# uartConverter.net
KiCad netlist of a schematic drawn in EAGLE
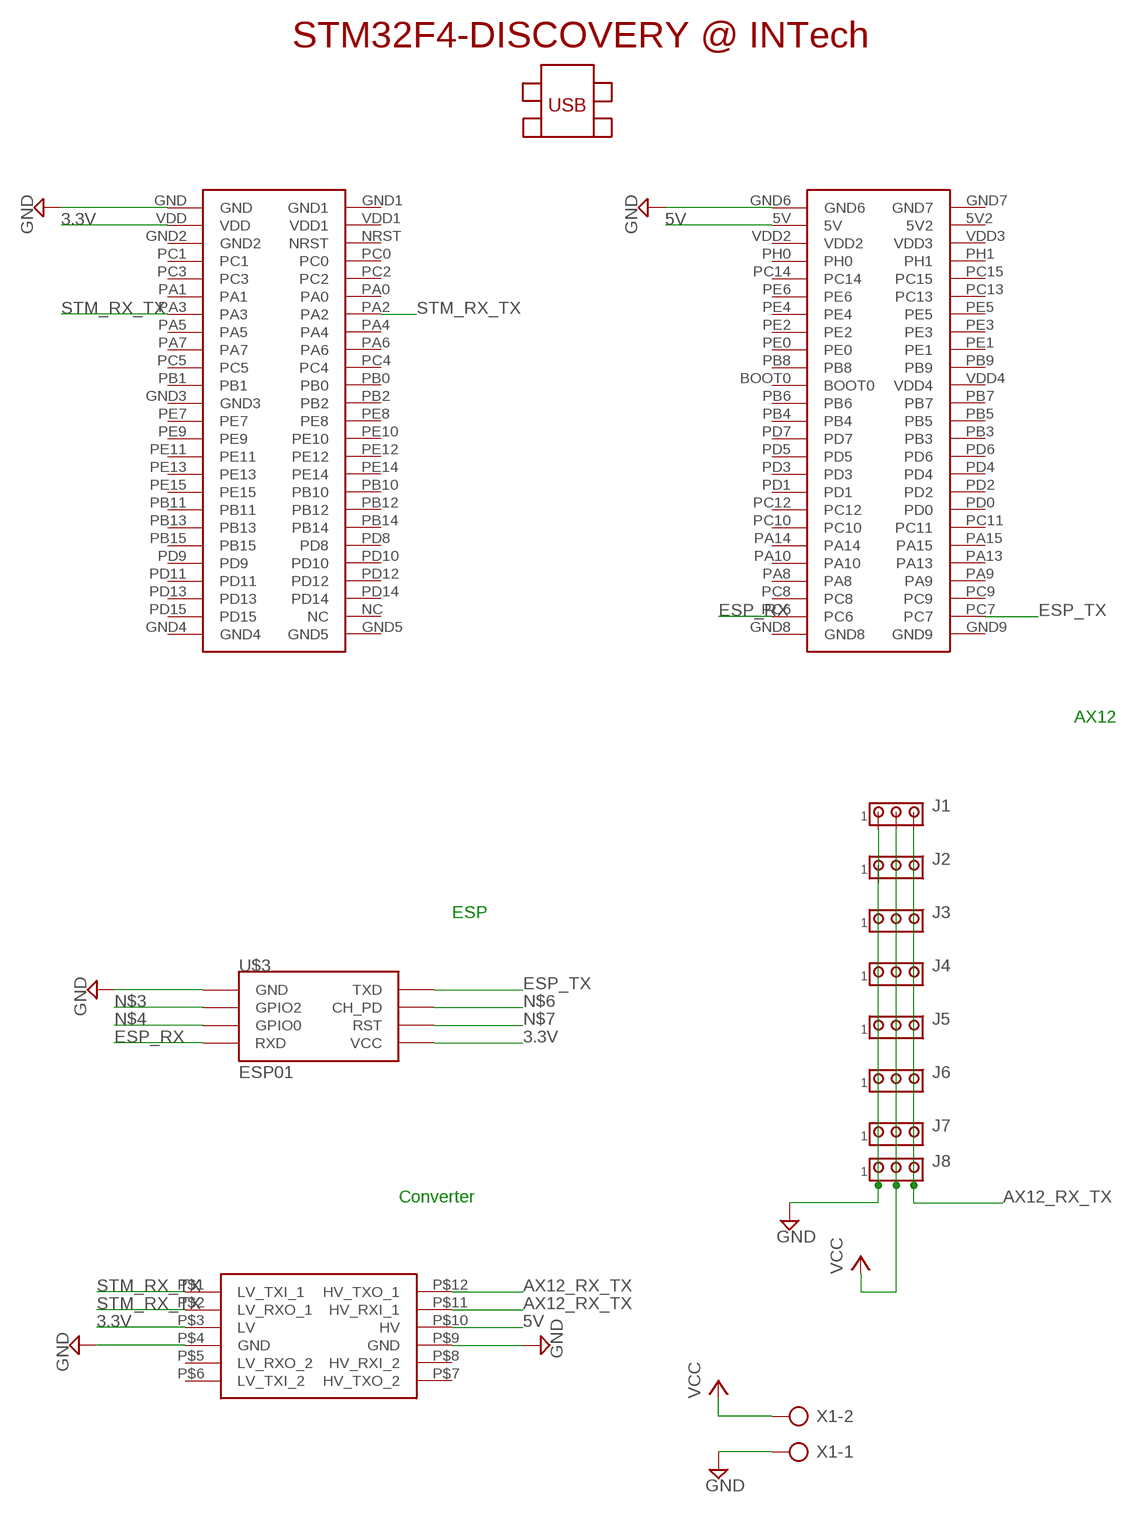
[diagram p0: schematic, sheet 1]

(export (version "E")
  (design (tool "Eeschema 10.0.6"))
  (components
    (comp (ref "J1")
      (value "MTA03-100")
      (footprint "eagle-import:10X03MTA")
      (libsource (lib "eagle-import") (part "MTA03-100"))
    )
    (comp (ref "J2")
      (value "MTA03-100")
      (footprint "eagle-import:10X03MTA")
      (libsource (lib "eagle-import") (part "MTA03-100"))
    )
    (comp (ref "J3")
      (value "MTA03-100")
      (footprint "eagle-import:10X03MTA")
      (libsource (lib "eagle-import") (part "MTA03-100"))
    )
    (comp (ref "J4")
      (value "MTA03-100")
      (footprint "eagle-import:10X03MTA")
      (libsource (lib "eagle-import") (part "MTA03-100"))
    )
    (comp (ref "J5")
      (value "MTA03-100")
      (footprint "eagle-import:10X03MTA")
      (libsource (lib "eagle-import") (part "MTA03-100"))
    )
    (comp (ref "J6")
      (value "MTA03-100")
      (footprint "eagle-import:10X03MTA")
      (libsource (lib "eagle-import") (part "MTA03-100"))
    )
    (comp (ref "J7")
      (value "MTA03-100")
      (footprint "eagle-import:10X03MTA")
      (libsource (lib "eagle-import") (part "MTA03-100"))
    )
    (comp (ref "J8")
      (value "MTA03-100")
      (footprint "eagle-import:10X03MTA")
      (libsource (lib "eagle-import") (part "MTA03-100"))
    )
    (comp (ref "U$1")
      (value "LOGIC_LEVEL_CONVERTER")
      (footprint "eagle-import:LOGIC_LEVEL_CONVERTER")
      (libsource (lib "eagle-import") (part "LOGIC_LEVEL_CONVERTER"))
    )
    (comp (ref "U$2")
      (value "STM32F4-DISCOVERY")
      (footprint "eagle-import:STM32F4-DISCOVERY")
      (libsource (lib "eagle-import") (part "STM32F4-DISCOVERY"))
    )
    (comp (ref "U$3")
      (value "ESP01")
      (footprint "eagle-import:ESP01")
      (libsource (lib "eagle-import") (part "ESP01"))
    )
    (comp (ref "X1")
      (value "AK300/2")
      (footprint "eagle-import:AK300_2")
      (libsource (lib "eagle-import") (part "AK300/2"))
    )
  )
  (nets
    (net (code "1") (name "/3.3V") (class "Default")
      (node (ref "U$1") (pin "P$3") (pinfunction "LV_P$3") (pintype "bidirectional"))
      (node (ref "U$2") (pin "VDD") (pinfunction "VDD_VDD") (pintype "bidirectional"))
      (node (ref "U$3") (pin "VCC") (pinfunction "VCC_VCC") (pintype "bidirectional"))
    )
    (net (code "2") (name "/5V") (class "Default")
      (node (ref "U$1") (pin "P$10") (pinfunction "HV_P$10") (pintype "bidirectional"))
      (node (ref "U$2") (pin "5V") (pinfunction "5V_5V") (pintype "bidirectional"))
    )
    (net (code "3") (name "/AX12_RX_TX") (class "Default")
      (node (ref "J1") (pin "3") (pinfunction "3_3") (pintype "passive"))
      (node (ref "J2") (pin "3") (pinfunction "3_3") (pintype "passive"))
      (node (ref "J3") (pin "3") (pinfunction "3_3") (pintype "passive"))
      (node (ref "J4") (pin "3") (pinfunction "3_3") (pintype "passive"))
      (node (ref "J5") (pin "3") (pinfunction "3_3") (pintype "passive"))
      (node (ref "J6") (pin "3") (pinfunction "3_3") (pintype "passive"))
      (node (ref "J7") (pin "3") (pinfunction "3_3") (pintype "passive"))
      (node (ref "J8") (pin "3") (pinfunction "3_3") (pintype "passive"))
      (node (ref "U$1") (pin "P$11") (pinfunction "HV_RXI_1_P$11") (pintype "bidirectional"))
      (node (ref "U$1") (pin "P$12") (pinfunction "HV_TXO_1_P$12") (pintype "bidirectional"))
    )
    (net (code "4") (name "/ESP_RX") (class "Default")
      (node (ref "U$2") (pin "PC6") (pinfunction "PC6_PC6") (pintype "bidirectional"))
      (node (ref "U$3") (pin "RX") (pinfunction "RXD_RX") (pintype "bidirectional"))
    )
    (net (code "5") (name "/ESP_TX") (class "Default")
      (node (ref "U$2") (pin "PC7") (pinfunction "PC7_PC7") (pintype "bidirectional"))
      (node (ref "U$3") (pin "TX") (pinfunction "TXD_TX") (pintype "bidirectional"))
    )
    (net (code "6") (name "/N$3") (class "Default")
      (node (ref "U$3") (pin "GPIO2") (pinfunction "GPIO2_GPIO2") (pintype "bidirectional"))
    )
    (net (code "7") (name "/N$4") (class "Default")
      (node (ref "U$3") (pin "GPIO0") (pinfunction "GPIO0_GPIO0") (pintype "bidirectional"))
    )
    (net (code "8") (name "/N$6") (class "Default")
      (node (ref "U$3") (pin "CH_PD") (pinfunction "CH_PD_CH_PD") (pintype "bidirectional"))
    )
    (net (code "9") (name "/N$7") (class "Default")
      (node (ref "U$3") (pin "RST") (pinfunction "RST_RST") (pintype "bidirectional"))
    )
    (net (code "10") (name "/STM_RX_TX") (class "Default")
      (node (ref "U$1") (pin "P$1") (pinfunction "LV_TXI_1_P$1") (pintype "bidirectional"))
      (node (ref "U$1") (pin "P$2") (pinfunction "LV_RXO_1_P$2") (pintype "bidirectional"))
      (node (ref "U$2") (pin "PA2") (pinfunction "PA2_PA2") (pintype "bidirectional"))
      (node (ref "U$2") (pin "PA3") (pinfunction "PA3_PA3") (pintype "bidirectional"))
    )
    (net (code "11") (name "GND") (class "Default")
      (node (ref "J1") (pin "1") (pinfunction "1_1") (pintype "passive"))
      (node (ref "J2") (pin "1") (pinfunction "1_1") (pintype "passive"))
      (node (ref "J3") (pin "1") (pinfunction "1_1") (pintype "passive"))
      (node (ref "J4") (pin "1") (pinfunction "1_1") (pintype "passive"))
      (node (ref "J5") (pin "1") (pinfunction "1_1") (pintype "passive"))
      (node (ref "J6") (pin "1") (pinfunction "1_1") (pintype "passive"))
      (node (ref "J7") (pin "1") (pinfunction "1_1") (pintype "passive"))
      (node (ref "J8") (pin "1") (pinfunction "1_1") (pintype "passive"))
      (node (ref "U$1") (pin "P$4") (pinfunction "GND_P$4") (pintype "bidirectional"))
      (node (ref "U$1") (pin "P$9") (pinfunction "GND_P$9") (pintype "bidirectional"))
      (node (ref "U$2") (pin "GND") (pinfunction "GND_GND") (pintype "bidirectional"))
      (node (ref "U$2") (pin "GND6") (pinfunction "GND6_GND6") (pintype "bidirectional"))
      (node (ref "U$3") (pin "GND") (pinfunction "GND_GND") (pintype "bidirectional"))
      (node (ref "X1") (pin "1") (pinfunction "KL_1") (pintype "passive"))
    )
    (net (code "12") (name "VCC") (class "Default")
      (node (ref "J1") (pin "2") (pinfunction "2_2") (pintype "passive"))
      (node (ref "J2") (pin "2") (pinfunction "2_2") (pintype "passive"))
      (node (ref "J3") (pin "2") (pinfunction "2_2") (pintype "passive"))
      (node (ref "J4") (pin "2") (pinfunction "2_2") (pintype "passive"))
      (node (ref "J5") (pin "2") (pinfunction "2_2") (pintype "passive"))
      (node (ref "J6") (pin "2") (pinfunction "2_2") (pintype "passive"))
      (node (ref "J7") (pin "2") (pinfunction "2_2") (pintype "passive"))
      (node (ref "J8") (pin "2") (pinfunction "2_2") (pintype "passive"))
      (node (ref "X1") (pin "2") (pinfunction "KL_2") (pintype "passive"))
    )
    (net (code "13") (name "unconnected-(U$1-HV_RXI_2-PadP$8)") (class "Default")
      (node (ref "U$1") (pin "P$8") (pinfunction "HV_RXI_2_P$8") (pintype "bidirectional"))
    )
    (net (code "14") (name "unconnected-(U$1-HV_TXO_2-PadP$7)") (class "Default")
      (node (ref "U$1") (pin "P$7") (pinfunction "HV_TXO_2_P$7") (pintype "bidirectional"))
    )
    (net (code "15") (name "unconnected-(U$1-LV_RXO_2-PadP$5)") (class "Default")
      (node (ref "U$1") (pin "P$5") (pinfunction "LV_RXO_2_P$5") (pintype "bidirectional"))
    )
    (net (code "16") (name "unconnected-(U$1-LV_TXI_2-PadP$6)") (class "Default")
      (node (ref "U$1") (pin "P$6") (pinfunction "LV_TXI_2_P$6") (pintype "bidirectional"))
    )
    (net (code "17") (name "unconnected-(U$2-Pad5V2)") (class "Default")
      (node (ref "U$2") (pin "5V2") (pinfunction "5V2_5V2") (pintype "bidirectional"))
    )
    (net (code "18") (name "unconnected-(U$2-PadBOOT0)") (class "Default")
      (node (ref "U$2") (pin "BOOT0") (pinfunction "BOOT0_BOOT0") (pintype "bidirectional"))
    )
    (net (code "19") (name "unconnected-(U$2-PadGND1)") (class "Default")
      (node (ref "U$2") (pin "GND1") (pinfunction "GND1_GND1") (pintype "bidirectional"))
    )
    (net (code "20") (name "unconnected-(U$2-PadGND2)") (class "Default")
      (node (ref "U$2") (pin "GND2") (pinfunction "GND2_GND2") (pintype "bidirectional"))
    )
    (net (code "21") (name "unconnected-(U$2-PadGND3)") (class "Default")
      (node (ref "U$2") (pin "GND3") (pinfunction "GND3_GND3") (pintype "bidirectional"))
    )
    (net (code "22") (name "unconnected-(U$2-PadGND4)") (class "Default")
      (node (ref "U$2") (pin "GND4") (pinfunction "GND4_GND4") (pintype "bidirectional"))
    )
    (net (code "23") (name "unconnected-(U$2-PadGND5)") (class "Default")
      (node (ref "U$2") (pin "GND5") (pinfunction "GND5_GND5") (pintype "bidirectional"))
    )
    (net (code "24") (name "unconnected-(U$2-PadGND7)") (class "Default")
      (node (ref "U$2") (pin "GND7") (pinfunction "GND7_GND7") (pintype "bidirectional"))
    )
    (net (code "25") (name "unconnected-(U$2-PadGND8)") (class "Default")
      (node (ref "U$2") (pin "GND8") (pinfunction "GND8_GND8") (pintype "bidirectional"))
    )
    (net (code "26") (name "unconnected-(U$2-PadGND9)") (class "Default")
      (node (ref "U$2") (pin "GND9") (pinfunction "GND9_GND9") (pintype "bidirectional"))
    )
    (net (code "27") (name "unconnected-(U$2-PadNC)") (class "Default")
      (node (ref "U$2") (pin "NC") (pinfunction "NC_NC") (pintype "bidirectional"))
    )
    (net (code "28") (name "unconnected-(U$2-PadNRST)") (class "Default")
      (node (ref "U$2") (pin "NRST") (pinfunction "NRST_NRST") (pintype "bidirectional"))
    )
    (net (code "29") (name "unconnected-(U$2-PadPA0)") (class "Default")
      (node (ref "U$2") (pin "PA0") (pinfunction "PA0_PA0") (pintype "bidirectional"))
    )
    (net (code "30") (name "unconnected-(U$2-PadPA1)") (class "Default")
      (node (ref "U$2") (pin "PA1") (pinfunction "PA1_PA1") (pintype "bidirectional"))
    )
    (net (code "31") (name "unconnected-(U$2-PadPA4)") (class "Default")
      (node (ref "U$2") (pin "PA4") (pinfunction "PA4_PA4") (pintype "bidirectional"))
    )
    (net (code "32") (name "unconnected-(U$2-PadPA5)") (class "Default")
      (node (ref "U$2") (pin "PA5") (pinfunction "PA5_PA5") (pintype "bidirectional"))
    )
    (net (code "33") (name "unconnected-(U$2-PadPA6)") (class "Default")
      (node (ref "U$2") (pin "PA6") (pinfunction "PA6_PA6") (pintype "bidirectional"))
    )
    (net (code "34") (name "unconnected-(U$2-PadPA7)") (class "Default")
      (node (ref "U$2") (pin "PA7") (pinfunction "PA7_PA7") (pintype "bidirectional"))
    )
    (net (code "35") (name "unconnected-(U$2-PadPA8)") (class "Default")
      (node (ref "U$2") (pin "PA8") (pinfunction "PA8_PA8") (pintype "bidirectional"))
    )
    (net (code "36") (name "unconnected-(U$2-PadPA9)") (class "Default")
      (node (ref "U$2") (pin "PA9") (pinfunction "PA9_PA9") (pintype "bidirectional"))
    )
    (net (code "37") (name "unconnected-(U$2-PadPA10)") (class "Default")
      (node (ref "U$2") (pin "PA10") (pinfunction "PA10_PA10") (pintype "bidirectional"))
    )
    (net (code "38") (name "unconnected-(U$2-PadPA13)") (class "Default")
      (node (ref "U$2") (pin "PA13") (pinfunction "PA13_PA13") (pintype "bidirectional"))
    )
    (net (code "39") (name "unconnected-(U$2-PadPA14)") (class "Default")
      (node (ref "U$2") (pin "PA14") (pinfunction "PA14_PA14") (pintype "bidirectional"))
    )
    (net (code "40") (name "unconnected-(U$2-PadPA15)") (class "Default")
      (node (ref "U$2") (pin "PA15") (pinfunction "PA15_PA15") (pintype "bidirectional"))
    )
    (net (code "41") (name "unconnected-(U$2-PadPB0)") (class "Default")
      (node (ref "U$2") (pin "PB0") (pinfunction "PB0_PB0") (pintype "bidirectional"))
    )
    (net (code "42") (name "unconnected-(U$2-PadPB1)") (class "Default")
      (node (ref "U$2") (pin "PB1") (pinfunction "PB1_PB1") (pintype "bidirectional"))
    )
    (net (code "43") (name "unconnected-(U$2-PadPB2)") (class "Default")
      (node (ref "U$2") (pin "PB2") (pinfunction "PB2_PB2") (pintype "bidirectional"))
    )
    (net (code "44") (name "unconnected-(U$2-PadPB3)") (class "Default")
      (node (ref "U$2") (pin "PB3") (pinfunction "PB3_PB3") (pintype "bidirectional"))
    )
    (net (code "45") (name "unconnected-(U$2-PadPB4)") (class "Default")
      (node (ref "U$2") (pin "PB4") (pinfunction "PB4_PB4") (pintype "bidirectional"))
    )
    (net (code "46") (name "unconnected-(U$2-PadPB5)") (class "Default")
      (node (ref "U$2") (pin "PB5") (pinfunction "PB5_PB5") (pintype "bidirectional"))
    )
    (net (code "47") (name "unconnected-(U$2-PadPB6)") (class "Default")
      (node (ref "U$2") (pin "PB6") (pinfunction "PB6_PB6") (pintype "bidirectional"))
    )
    (net (code "48") (name "unconnected-(U$2-PadPB7)") (class "Default")
      (node (ref "U$2") (pin "PB7") (pinfunction "PB7_PB7") (pintype "bidirectional"))
    )
    (net (code "49") (name "unconnected-(U$2-PadPB8)") (class "Default")
      (node (ref "U$2") (pin "PB8") (pinfunction "PB8_PB8") (pintype "bidirectional"))
    )
    (net (code "50") (name "unconnected-(U$2-PadPB9)") (class "Default")
      (node (ref "U$2") (pin "PB9") (pinfunction "PB9_PB9") (pintype "bidirectional"))
    )
    (net (code "51") (name "unconnected-(U$2-PadPB10)") (class "Default")
      (node (ref "U$2") (pin "PB10") (pinfunction "PB10_PB10") (pintype "bidirectional"))
    )
    (net (code "52") (name "unconnected-(U$2-PadPB11)") (class "Default")
      (node (ref "U$2") (pin "PB11") (pinfunction "PB11_PB11") (pintype "bidirectional"))
    )
    (net (code "53") (name "unconnected-(U$2-PadPB12)") (class "Default")
      (node (ref "U$2") (pin "PB12") (pinfunction "PB12_PB12") (pintype "bidirectional"))
    )
    (net (code "54") (name "unconnected-(U$2-PadPB13)") (class "Default")
      (node (ref "U$2") (pin "PB13") (pinfunction "PB13_PB13") (pintype "bidirectional"))
    )
    (net (code "55") (name "unconnected-(U$2-PadPB14)") (class "Default")
      (node (ref "U$2") (pin "PB14") (pinfunction "PB14_PB14") (pintype "bidirectional"))
    )
    (net (code "56") (name "unconnected-(U$2-PadPB15)") (class "Default")
      (node (ref "U$2") (pin "PB15") (pinfunction "PB15_PB15") (pintype "bidirectional"))
    )
    (net (code "57") (name "unconnected-(U$2-PadPC0)") (class "Default")
      (node (ref "U$2") (pin "PC0") (pinfunction "PC0_PC0") (pintype "bidirectional"))
    )
    (net (code "58") (name "unconnected-(U$2-PadPC1)") (class "Default")
      (node (ref "U$2") (pin "PC1") (pinfunction "PC1_PC1") (pintype "bidirectional"))
    )
    (net (code "59") (name "unconnected-(U$2-PadPC2)") (class "Default")
      (node (ref "U$2") (pin "PC2") (pinfunction "PC2_PC2") (pintype "bidirectional"))
    )
    (net (code "60") (name "unconnected-(U$2-PadPC3)") (class "Default")
      (node (ref "U$2") (pin "PC3") (pinfunction "PC3_PC3") (pintype "bidirectional"))
    )
    (net (code "61") (name "unconnected-(U$2-PadPC4)") (class "Default")
      (node (ref "U$2") (pin "PC4") (pinfunction "PC4_PC4") (pintype "bidirectional"))
    )
    (net (code "62") (name "unconnected-(U$2-PadPC5)") (class "Default")
      (node (ref "U$2") (pin "PC5") (pinfunction "PC5_PC5") (pintype "bidirectional"))
    )
    (net (code "63") (name "unconnected-(U$2-PadPC8)") (class "Default")
      (node (ref "U$2") (pin "PC8") (pinfunction "PC8_PC8") (pintype "bidirectional"))
    )
    (net (code "64") (name "unconnected-(U$2-PadPC9)") (class "Default")
      (node (ref "U$2") (pin "PC9") (pinfunction "PC9_PC9") (pintype "bidirectional"))
    )
    (net (code "65") (name "unconnected-(U$2-PadPC10)") (class "Default")
      (node (ref "U$2") (pin "PC10") (pinfunction "PC10_PC10") (pintype "bidirectional"))
    )
    (net (code "66") (name "unconnected-(U$2-PadPC11)") (class "Default")
      (node (ref "U$2") (pin "PC11") (pinfunction "PC11_PC11") (pintype "bidirectional"))
    )
    (net (code "67") (name "unconnected-(U$2-PadPC12)") (class "Default")
      (node (ref "U$2") (pin "PC12") (pinfunction "PC12_PC12") (pintype "bidirectional"))
    )
    (net (code "68") (name "unconnected-(U$2-PadPC13)") (class "Default")
      (node (ref "U$2") (pin "PC13") (pinfunction "PC13_PC13") (pintype "bidirectional"))
    )
    (net (code "69") (name "unconnected-(U$2-PadPC14)") (class "Default")
      (node (ref "U$2") (pin "PC14") (pinfunction "PC14_PC14") (pintype "bidirectional"))
    )
    (net (code "70") (name "unconnected-(U$2-PadPC15)") (class "Default")
      (node (ref "U$2") (pin "PC15") (pinfunction "PC15_PC15") (pintype "bidirectional"))
    )
    (net (code "71") (name "unconnected-(U$2-PadPD0)") (class "Default")
      (node (ref "U$2") (pin "PD0") (pinfunction "PD0_PD0") (pintype "bidirectional"))
    )
    (net (code "72") (name "unconnected-(U$2-PadPD1)") (class "Default")
      (node (ref "U$2") (pin "PD1") (pinfunction "PD1_PD1") (pintype "bidirectional"))
    )
    (net (code "73") (name "unconnected-(U$2-PadPD2)") (class "Default")
      (node (ref "U$2") (pin "PD2") (pinfunction "PD2_PD2") (pintype "bidirectional"))
    )
    (net (code "74") (name "unconnected-(U$2-PadPD3)") (class "Default")
      (node (ref "U$2") (pin "PD3") (pinfunction "PD3_PD3") (pintype "bidirectional"))
    )
    (net (code "75") (name "unconnected-(U$2-PadPD4)") (class "Default")
      (node (ref "U$2") (pin "PD4") (pinfunction "PD4_PD4") (pintype "bidirectional"))
    )
    (net (code "76") (name "unconnected-(U$2-PadPD5)") (class "Default")
      (node (ref "U$2") (pin "PD5") (pinfunction "PD5_PD5") (pintype "bidirectional"))
    )
    (net (code "77") (name "unconnected-(U$2-PadPD6)") (class "Default")
      (node (ref "U$2") (pin "PD6") (pinfunction "PD6_PD6") (pintype "bidirectional"))
    )
    (net (code "78") (name "unconnected-(U$2-PadPD7)") (class "Default")
      (node (ref "U$2") (pin "PD7") (pinfunction "PD7_PD7") (pintype "bidirectional"))
    )
    (net (code "79") (name "unconnected-(U$2-PadPD8)") (class "Default")
      (node (ref "U$2") (pin "PD8") (pinfunction "PD8_PD8") (pintype "bidirectional"))
    )
    (net (code "80") (name "unconnected-(U$2-PadPD9)") (class "Default")
      (node (ref "U$2") (pin "PD9") (pinfunction "PD9_PD9") (pintype "bidirectional"))
    )
    (net (code "81") (name "unconnected-(U$2-PadPD10)") (class "Default")
      (node (ref "U$2") (pin "PD10") (pinfunction "PD10_PD10") (pintype "bidirectional"))
    )
    (net (code "82") (name "unconnected-(U$2-PadPD11)") (class "Default")
      (node (ref "U$2") (pin "PD11") (pinfunction "PD11_PD11") (pintype "bidirectional"))
    )
    (net (code "83") (name "unconnected-(U$2-PadPD12)") (class "Default")
      (node (ref "U$2") (pin "PD12") (pinfunction "PD12_PD12") (pintype "bidirectional"))
    )
    (net (code "84") (name "unconnected-(U$2-PadPD13)") (class "Default")
      (node (ref "U$2") (pin "PD13") (pinfunction "PD13_PD13") (pintype "bidirectional"))
    )
    (net (code "85") (name "unconnected-(U$2-PadPD14)") (class "Default")
      (node (ref "U$2") (pin "PD14") (pinfunction "PD14_PD14") (pintype "bidirectional"))
    )
    (net (code "86") (name "unconnected-(U$2-PadPD15)") (class "Default")
      (node (ref "U$2") (pin "PD15") (pinfunction "PD15_PD15") (pintype "bidirectional"))
    )
    (net (code "87") (name "unconnected-(U$2-PadPE0)") (class "Default")
      (node (ref "U$2") (pin "PE0") (pinfunction "PE0_PE0") (pintype "bidirectional"))
    )
    (net (code "88") (name "unconnected-(U$2-PadPE1)") (class "Default")
      (node (ref "U$2") (pin "PE1") (pinfunction "PE1_PE1") (pintype "bidirectional"))
    )
    (net (code "89") (name "unconnected-(U$2-PadPE2)") (class "Default")
      (node (ref "U$2") (pin "PE2") (pinfunction "PE2_PE2") (pintype "bidirectional"))
    )
    (net (code "90") (name "unconnected-(U$2-PadPE3)") (class "Default")
      (node (ref "U$2") (pin "PE3") (pinfunction "PE3_PE3") (pintype "bidirectional"))
    )
    (net (code "91") (name "unconnected-(U$2-PadPE4)") (class "Default")
      (node (ref "U$2") (pin "PE4") (pinfunction "PE4_PE4") (pintype "bidirectional"))
    )
    (net (code "92") (name "unconnected-(U$2-PadPE5)") (class "Default")
      (node (ref "U$2") (pin "PE5") (pinfunction "PE5_PE5") (pintype "bidirectional"))
    )
    (net (code "93") (name "unconnected-(U$2-PadPE6)") (class "Default")
      (node (ref "U$2") (pin "PE6") (pinfunction "PE6_PE6") (pintype "bidirectional"))
    )
    (net (code "94") (name "unconnected-(U$2-PadPE7)") (class "Default")
      (node (ref "U$2") (pin "PE7") (pinfunction "PE7_PE7") (pintype "bidirectional"))
    )
    (net (code "95") (name "unconnected-(U$2-PadPE8)") (class "Default")
      (node (ref "U$2") (pin "PE8") (pinfunction "PE8_PE8") (pintype "bidirectional"))
    )
    (net (code "96") (name "unconnected-(U$2-PadPE9)") (class "Default")
      (node (ref "U$2") (pin "PE9") (pinfunction "PE9_PE9") (pintype "bidirectional"))
    )
    (net (code "97") (name "unconnected-(U$2-PadPE10)") (class "Default")
      (node (ref "U$2") (pin "PE10") (pinfunction "PE10_PE10") (pintype "bidirectional"))
    )
    (net (code "98") (name "unconnected-(U$2-PadPE11)") (class "Default")
      (node (ref "U$2") (pin "PE11") (pinfunction "PE11_PE11") (pintype "bidirectional"))
    )
    (net (code "99") (name "unconnected-(U$2-PadPE12)") (class "Default")
      (node (ref "U$2") (pin "PE12") (pinfunction "PE12_PE12") (pintype "bidirectional"))
    )
    (net (code "100") (name "unconnected-(U$2-PadPE13)") (class "Default")
      (node (ref "U$2") (pin "PE13") (pinfunction "PE13_PE13") (pintype "bidirectional"))
    )
    (net (code "101") (name "unconnected-(U$2-PadPE14)") (class "Default")
      (node (ref "U$2") (pin "PE14") (pinfunction "PE14_PE14") (pintype "bidirectional"))
    )
    (net (code "102") (name "unconnected-(U$2-PadPE15)") (class "Default")
      (node (ref "U$2") (pin "PE15") (pinfunction "PE15_PE15") (pintype "bidirectional"))
    )
    (net (code "103") (name "unconnected-(U$2-PadPH0)") (class "Default")
      (node (ref "U$2") (pin "PH0") (pinfunction "PH0_PH0") (pintype "bidirectional"))
    )
    (net (code "104") (name "unconnected-(U$2-PadPH1)") (class "Default")
      (node (ref "U$2") (pin "PH1") (pinfunction "PH1_PH1") (pintype "bidirectional"))
    )
    (net (code "105") (name "unconnected-(U$2-PadVDD1)") (class "Default")
      (node (ref "U$2") (pin "VDD1") (pinfunction "VDD1_VDD1") (pintype "bidirectional"))
    )
    (net (code "106") (name "unconnected-(U$2-PadVDD2)") (class "Default")
      (node (ref "U$2") (pin "VDD2") (pinfunction "VDD2_VDD2") (pintype "bidirectional"))
    )
    (net (code "107") (name "unconnected-(U$2-PadVDD3)") (class "Default")
      (node (ref "U$2") (pin "VDD3") (pinfunction "VDD3_VDD3") (pintype "bidirectional"))
    )
    (net (code "108") (name "unconnected-(U$2-PadVDD4)") (class "Default")
      (node (ref "U$2") (pin "VDD4") (pinfunction "VDD4_VDD4") (pintype "bidirectional"))
    )
  )
)
